# parport.net
KiCad netlist of a schematic drawn in EAGLE
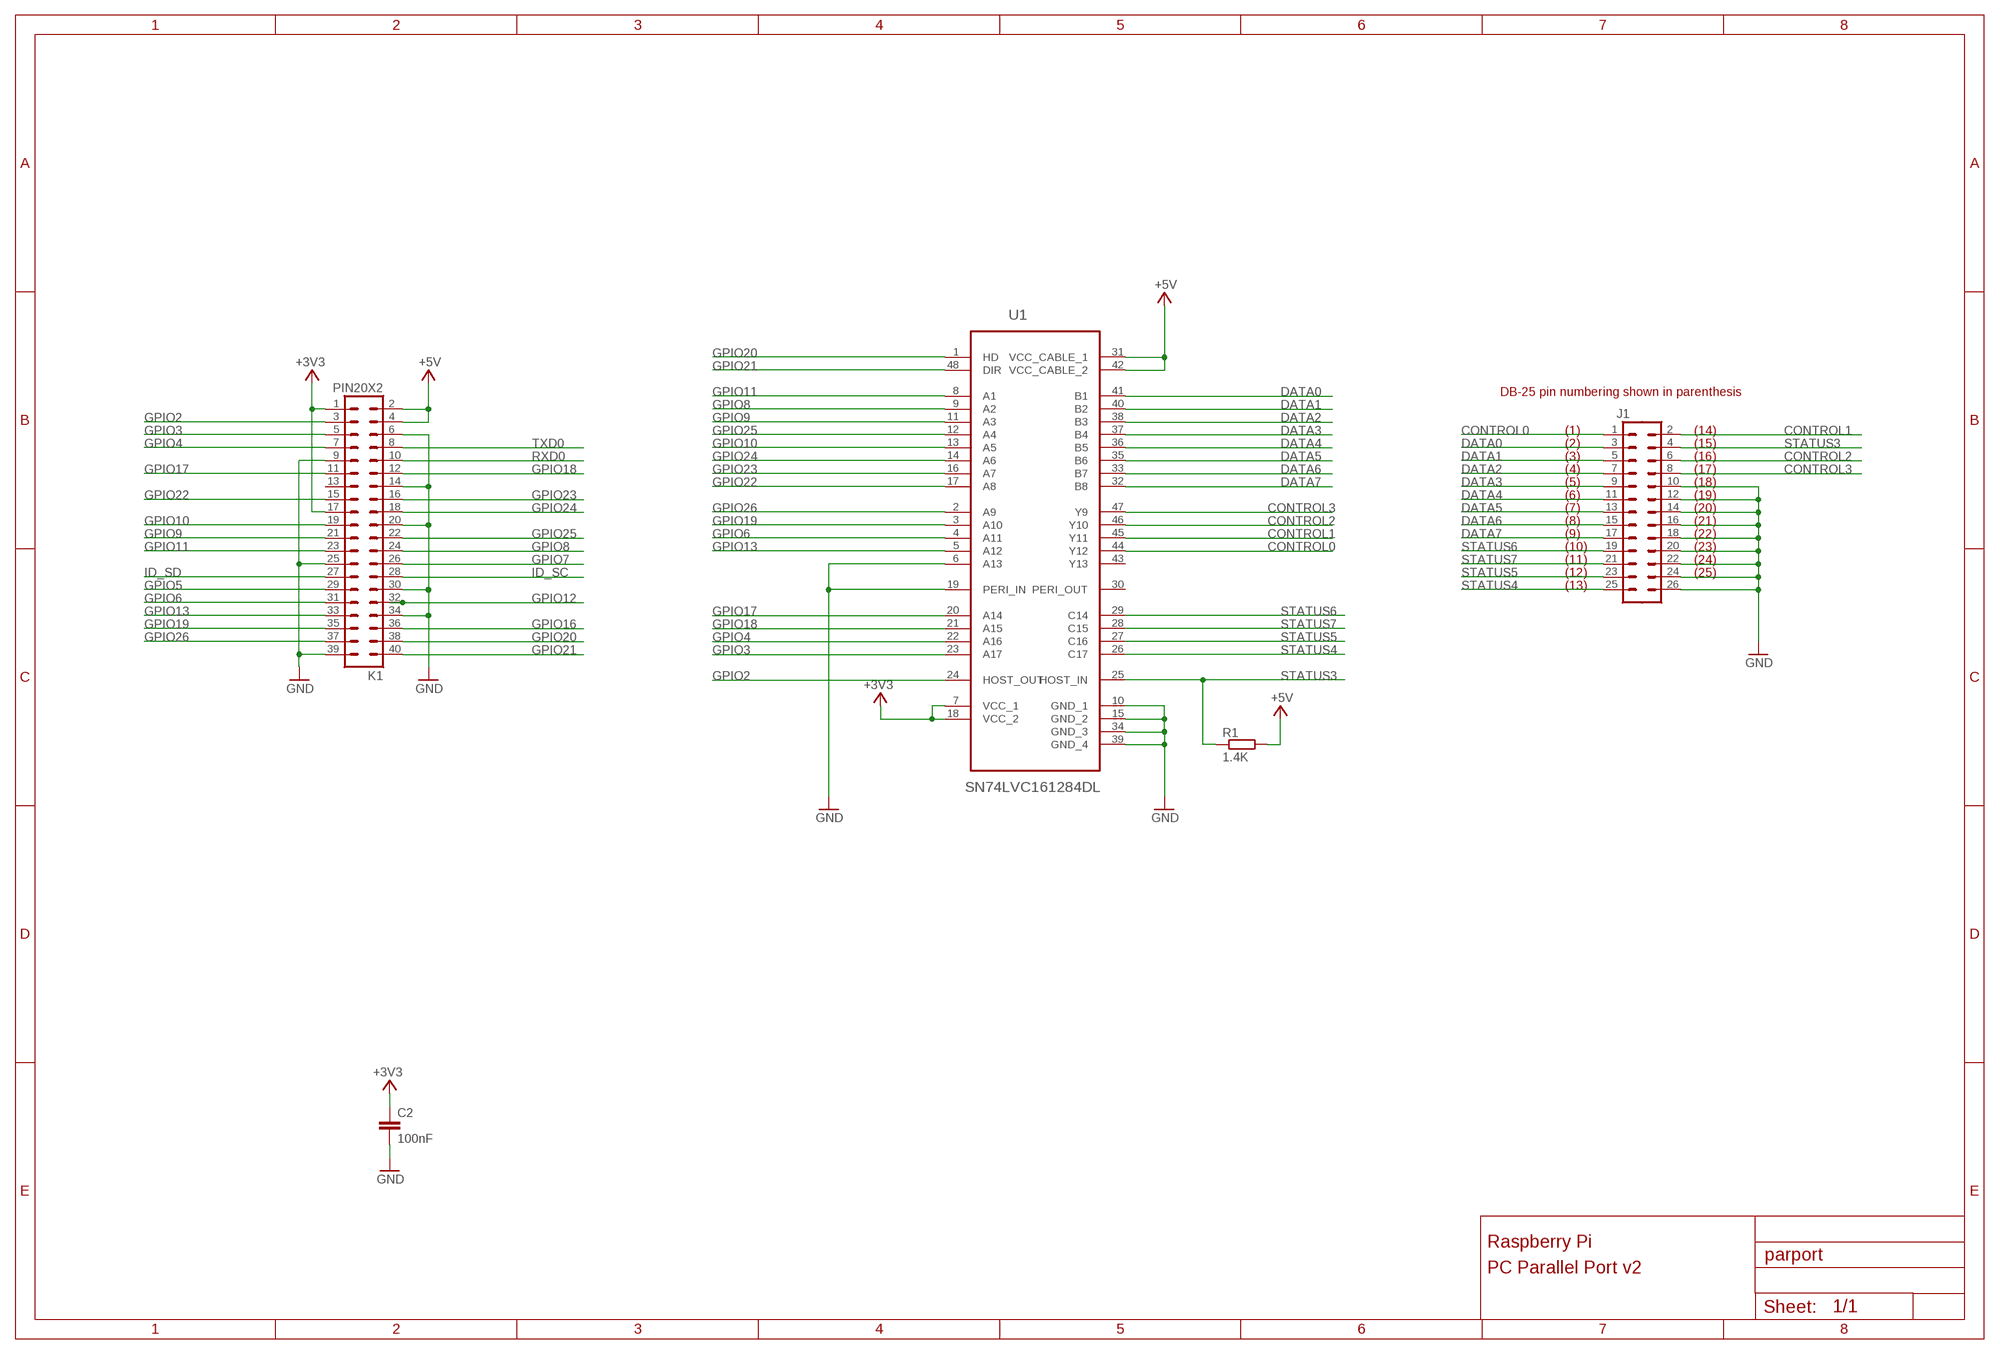
[diagram p0: schematic, sheet 1]

(export (version "E")
  (design (tool "Eeschema 10.0.6"))
  (components
    (comp (ref "C2")
      (value "100nF")
      (footprint "eagle-import:C0805")
      (libsource (lib "eagle-import") (part "C-EUC0805"))
    )
    (comp (ref "J1")
      (value "M13X22X13")
      (footprint "eagle-import:2X13")
      (libsource (lib "eagle-import") (part "M13X22X13"))
    )
    (comp (ref "K1")
      (value "PIN20X2")
      (footprint "eagle-import:PIN_20X2")
      (libsource (lib "eagle-import") (part "PIN20X2"))
    )
    (comp (ref "R1")
      (value "1.4K")
      (footprint "eagle-import:R0805")
      (libsource (lib "eagle-import") (part "R-EU_R0805"))
    )
    (comp (ref "U1")
      (value "SN74LVC161284DL")
      (footprint "eagle-import:SOP63P1035X279-48N")
      (libsource (lib "eagle-import") (part "SN74LVC161284DL"))
    )
  )
  (nets
    (net (code "1") (name "+3V3") (class "Default")
      (node (ref "C2") (pin "1") (pinfunction "1_1") (pintype "passive"))
      (node (ref "K1") (pin "1") (pinfunction "1_1") (pintype "passive"))
      (node (ref "K1") (pin "17") (pinfunction "17_17") (pintype "passive"))
      (node (ref "U1") (pin "18") (pinfunction "VCC_2_18") (pintype "input"))
      (node (ref "U1") (pin "7") (pinfunction "VCC_1_7") (pintype "input"))
    )
    (net (code "2") (name "+5V") (class "Default")
      (node (ref "K1") (pin "2") (pinfunction "2_2") (pintype "passive"))
      (node (ref "K1") (pin "4") (pinfunction "4_4") (pintype "passive"))
      (node (ref "R1") (pin "2") (pinfunction "2_2") (pintype "passive"))
      (node (ref "U1") (pin "31") (pinfunction "VCC_CABLE_1_31") (pintype "passive"))
      (node (ref "U1") (pin "42") (pinfunction "VCC_CABLE_2_42") (pintype "output"))
    )
    (net (code "3") (name "/CONTROL0") (class "Default")
      (node (ref "J1") (pin "1") (pinfunction "1_1") (pintype "passive"))
      (node (ref "U1") (pin "44") (pinfunction "Y12_44") (pintype "output"))
    )
    (net (code "4") (name "/CONTROL1") (class "Default")
      (node (ref "J1") (pin "2") (pinfunction "2_2") (pintype "passive"))
      (node (ref "U1") (pin "45") (pinfunction "Y11_45") (pintype "output"))
    )
    (net (code "5") (name "/CONTROL2") (class "Default")
      (node (ref "J1") (pin "6") (pinfunction "6_6") (pintype "passive"))
      (node (ref "U1") (pin "46") (pinfunction "Y10_46") (pintype "output"))
    )
    (net (code "6") (name "/CONTROL3") (class "Default")
      (node (ref "J1") (pin "8") (pinfunction "8_8") (pintype "passive"))
      (node (ref "U1") (pin "47") (pinfunction "Y9_47") (pintype "output"))
    )
    (net (code "7") (name "/DATA0") (class "Default")
      (node (ref "J1") (pin "3") (pinfunction "3_3") (pintype "passive"))
      (node (ref "U1") (pin "41") (pinfunction "B1_41") (pintype "output"))
    )
    (net (code "8") (name "/DATA1") (class "Default")
      (node (ref "J1") (pin "5") (pinfunction "5_5") (pintype "passive"))
      (node (ref "U1") (pin "40") (pinfunction "B2_40") (pintype "output"))
    )
    (net (code "9") (name "/DATA2") (class "Default")
      (node (ref "J1") (pin "7") (pinfunction "7_7") (pintype "passive"))
      (node (ref "U1") (pin "38") (pinfunction "B3_38") (pintype "output"))
    )
    (net (code "10") (name "/DATA3") (class "Default")
      (node (ref "J1") (pin "9") (pinfunction "9_9") (pintype "passive"))
      (node (ref "U1") (pin "37") (pinfunction "B4_37") (pintype "output"))
    )
    (net (code "11") (name "/DATA4") (class "Default")
      (node (ref "J1") (pin "11") (pinfunction "11_11") (pintype "passive"))
      (node (ref "U1") (pin "36") (pinfunction "B5_36") (pintype "output"))
    )
    (net (code "12") (name "/DATA5") (class "Default")
      (node (ref "J1") (pin "13") (pinfunction "13_13") (pintype "passive"))
      (node (ref "U1") (pin "35") (pinfunction "B6_35") (pintype "output"))
    )
    (net (code "13") (name "/DATA6") (class "Default")
      (node (ref "J1") (pin "15") (pinfunction "15_15") (pintype "passive"))
      (node (ref "U1") (pin "33") (pinfunction "B7_33") (pintype "output"))
    )
    (net (code "14") (name "/DATA7") (class "Default")
      (node (ref "J1") (pin "17") (pinfunction "17_17") (pintype "passive"))
      (node (ref "U1") (pin "32") (pinfunction "B8_32") (pintype "passive"))
    )
    (net (code "15") (name "/GPIO2") (class "Default")
      (node (ref "K1") (pin "3") (pinfunction "3_3") (pintype "passive"))
      (node (ref "U1") (pin "24") (pinfunction "HOST_OUT_24") (pintype "input"))
    )
    (net (code "16") (name "/GPIO3") (class "Default")
      (node (ref "K1") (pin "5") (pinfunction "5_5") (pintype "passive"))
      (node (ref "U1") (pin "23") (pinfunction "A17_23") (pintype "input"))
    )
    (net (code "17") (name "/GPIO4") (class "Default")
      (node (ref "K1") (pin "7") (pinfunction "7_7") (pintype "passive"))
      (node (ref "U1") (pin "22") (pinfunction "A16_22") (pintype "input"))
    )
    (net (code "18") (name "/GPIO5") (class "Default")
      (node (ref "K1") (pin "29") (pinfunction "29_29") (pintype "passive"))
    )
    (net (code "19") (name "/GPIO6") (class "Default")
      (node (ref "K1") (pin "31") (pinfunction "31_31") (pintype "passive"))
      (node (ref "U1") (pin "4") (pinfunction "A11_4") (pintype "power_in"))
    )
    (net (code "20") (name "/GPIO7") (class "Default")
      (node (ref "K1") (pin "26") (pinfunction "26_26") (pintype "passive"))
    )
    (net (code "21") (name "/GPIO8") (class "Default")
      (node (ref "K1") (pin "24") (pinfunction "24_24") (pintype "passive"))
      (node (ref "U1") (pin "9") (pinfunction "A2_9") (pintype "input"))
    )
    (net (code "22") (name "/GPIO9") (class "Default")
      (node (ref "K1") (pin "21") (pinfunction "21_21") (pintype "passive"))
      (node (ref "U1") (pin "11") (pinfunction "A3_11") (pintype "input"))
    )
    (net (code "23") (name "/GPIO10") (class "Default")
      (node (ref "K1") (pin "19") (pinfunction "19_19") (pintype "passive"))
      (node (ref "U1") (pin "13") (pinfunction "A5_13") (pintype "input"))
    )
    (net (code "24") (name "/GPIO11") (class "Default")
      (node (ref "K1") (pin "23") (pinfunction "23_23") (pintype "passive"))
      (node (ref "U1") (pin "8") (pinfunction "A1_8") (pintype "input"))
    )
    (net (code "25") (name "/GPIO12") (class "Default")
      (node (ref "K1") (pin "32") (pinfunction "32_32") (pintype "passive"))
    )
    (net (code "26") (name "/GPIO13") (class "Default")
      (node (ref "K1") (pin "33") (pinfunction "33_33") (pintype "passive"))
      (node (ref "U1") (pin "5") (pinfunction "A12_5") (pintype "input"))
    )
    (net (code "27") (name "/GPIO16") (class "Default")
      (node (ref "K1") (pin "36") (pinfunction "36_36") (pintype "passive"))
    )
    (net (code "28") (name "/GPIO17") (class "Default")
      (node (ref "K1") (pin "11") (pinfunction "11_11") (pintype "passive"))
      (node (ref "U1") (pin "20") (pinfunction "A14_20") (pintype "input"))
    )
    (net (code "29") (name "/GPIO18") (class "Default")
      (node (ref "K1") (pin "12") (pinfunction "12_12") (pintype "passive"))
      (node (ref "U1") (pin "21") (pinfunction "A15_21") (pintype "input"))
    )
    (net (code "30") (name "/GPIO19") (class "Default")
      (node (ref "K1") (pin "35") (pinfunction "35_35") (pintype "passive"))
      (node (ref "U1") (pin "3") (pinfunction "A10_3") (pintype "power_in"))
    )
    (net (code "31") (name "/GPIO20") (class "Default")
      (node (ref "K1") (pin "38") (pinfunction "38_38") (pintype "passive"))
      (node (ref "U1") (pin "1") (pinfunction "HD_1") (pintype "power_in"))
    )
    (net (code "32") (name "/GPIO21") (class "Default")
      (node (ref "K1") (pin "40") (pinfunction "40_40") (pintype "passive"))
      (node (ref "U1") (pin "48") (pinfunction "DIR_48") (pintype "output"))
    )
    (net (code "33") (name "/GPIO22") (class "Default")
      (node (ref "K1") (pin "15") (pinfunction "15_15") (pintype "passive"))
      (node (ref "U1") (pin "17") (pinfunction "A8_17") (pintype "input"))
    )
    (net (code "34") (name "/GPIO23") (class "Default")
      (node (ref "K1") (pin "16") (pinfunction "16_16") (pintype "passive"))
      (node (ref "U1") (pin "16") (pinfunction "A7_16") (pintype "input"))
    )
    (net (code "35") (name "/GPIO24") (class "Default")
      (node (ref "K1") (pin "18") (pinfunction "18_18") (pintype "passive"))
      (node (ref "U1") (pin "14") (pinfunction "A6_14") (pintype "input"))
    )
    (net (code "36") (name "/GPIO25") (class "Default")
      (node (ref "K1") (pin "22") (pinfunction "22_22") (pintype "passive"))
      (node (ref "U1") (pin "12") (pinfunction "A4_12") (pintype "input"))
    )
    (net (code "37") (name "/GPIO26") (class "Default")
      (node (ref "K1") (pin "37") (pinfunction "37_37") (pintype "passive"))
      (node (ref "U1") (pin "2") (pinfunction "A9_2") (pintype "power_in"))
    )
    (net (code "38") (name "/ID_SC") (class "Default")
      (node (ref "K1") (pin "28") (pinfunction "28_28") (pintype "passive"))
    )
    (net (code "39") (name "/ID_SD") (class "Default")
      (node (ref "K1") (pin "27") (pinfunction "27_27") (pintype "passive"))
    )
    (net (code "40") (name "/RXD0") (class "Default")
      (node (ref "K1") (pin "10") (pinfunction "10_10") (pintype "passive"))
    )
    (net (code "41") (name "/STATUS3") (class "Default")
      (node (ref "J1") (pin "4") (pinfunction "4_4") (pintype "passive"))
      (node (ref "R1") (pin "1") (pinfunction "1_1") (pintype "passive"))
      (node (ref "U1") (pin "25") (pinfunction "HOST_IN_25") (pintype "passive"))
    )
    (net (code "42") (name "/STATUS4") (class "Default")
      (node (ref "J1") (pin "25") (pinfunction "25_25") (pintype "passive"))
      (node (ref "U1") (pin "26") (pinfunction "C17_26") (pintype "passive"))
    )
    (net (code "43") (name "/STATUS5") (class "Default")
      (node (ref "J1") (pin "23") (pinfunction "23_23") (pintype "passive"))
      (node (ref "U1") (pin "27") (pinfunction "C16_27") (pintype "passive"))
    )
    (net (code "44") (name "/STATUS6") (class "Default")
      (node (ref "J1") (pin "19") (pinfunction "19_19") (pintype "passive"))
      (node (ref "U1") (pin "29") (pinfunction "C14_29") (pintype "passive"))
    )
    (net (code "45") (name "/STATUS7") (class "Default")
      (node (ref "J1") (pin "21") (pinfunction "21_21") (pintype "passive"))
      (node (ref "U1") (pin "28") (pinfunction "C15_28") (pintype "passive"))
    )
    (net (code "46") (name "/TXD0") (class "Default")
      (node (ref "K1") (pin "8") (pinfunction "8_8") (pintype "passive"))
    )
    (net (code "47") (name "GND") (class "Default")
      (node (ref "C2") (pin "2") (pinfunction "2_2") (pintype "passive"))
      (node (ref "J1") (pin "10") (pinfunction "10_10") (pintype "passive"))
      (node (ref "J1") (pin "12") (pinfunction "12_12") (pintype "passive"))
      (node (ref "J1") (pin "14") (pinfunction "14_14") (pintype "passive"))
      (node (ref "J1") (pin "16") (pinfunction "16_16") (pintype "passive"))
      (node (ref "J1") (pin "18") (pinfunction "18_18") (pintype "passive"))
      (node (ref "J1") (pin "20") (pinfunction "20_20") (pintype "passive"))
      (node (ref "J1") (pin "22") (pinfunction "22_22") (pintype "passive"))
      (node (ref "J1") (pin "24") (pinfunction "24_24") (pintype "passive"))
      (node (ref "J1") (pin "26") (pinfunction "26_26") (pintype "passive"))
      (node (ref "K1") (pin "14") (pinfunction "14_14") (pintype "passive"))
      (node (ref "K1") (pin "20") (pinfunction "20_20") (pintype "passive"))
      (node (ref "K1") (pin "25") (pinfunction "25_25") (pintype "passive"))
      (node (ref "K1") (pin "30") (pinfunction "30_30") (pintype "passive"))
      (node (ref "K1") (pin "34") (pinfunction "34_34") (pintype "passive"))
      (node (ref "K1") (pin "39") (pinfunction "39_39") (pintype "passive"))
      (node (ref "K1") (pin "6") (pinfunction "6_6") (pintype "passive"))
      (node (ref "K1") (pin "9") (pinfunction "9_9") (pintype "passive"))
      (node (ref "U1") (pin "10") (pinfunction "GND_1_10") (pintype "input"))
      (node (ref "U1") (pin "15") (pinfunction "GND_2_15") (pintype "input"))
      (node (ref "U1") (pin "19") (pinfunction "PERI_IN_19") (pintype "input"))
      (node (ref "U1") (pin "34") (pinfunction "GND_3_34") (pintype "output"))
      (node (ref "U1") (pin "39") (pinfunction "GND_4_39") (pintype "output"))
      (node (ref "U1") (pin "6") (pinfunction "A13_6") (pintype "input"))
    )
    (net (code "48") (name "unconnected-(K1-Pad13)") (class "Default")
      (node (ref "K1") (pin "13") (pinfunction "13_13") (pintype "passive"))
    )
    (net (code "49") (name "unconnected-(U1-PERI_OUT-Pad30)") (class "Default")
      (node (ref "U1") (pin "30") (pinfunction "PERI_OUT_30") (pintype "passive"))
    )
    (net (code "50") (name "unconnected-(U1-Y13-Pad43)") (class "Default")
      (node (ref "U1") (pin "43") (pinfunction "Y13_43") (pintype "output"))
    )
  )
)
